# POWER.net
KiCad netlist of a schematic drawn in Altium Designer
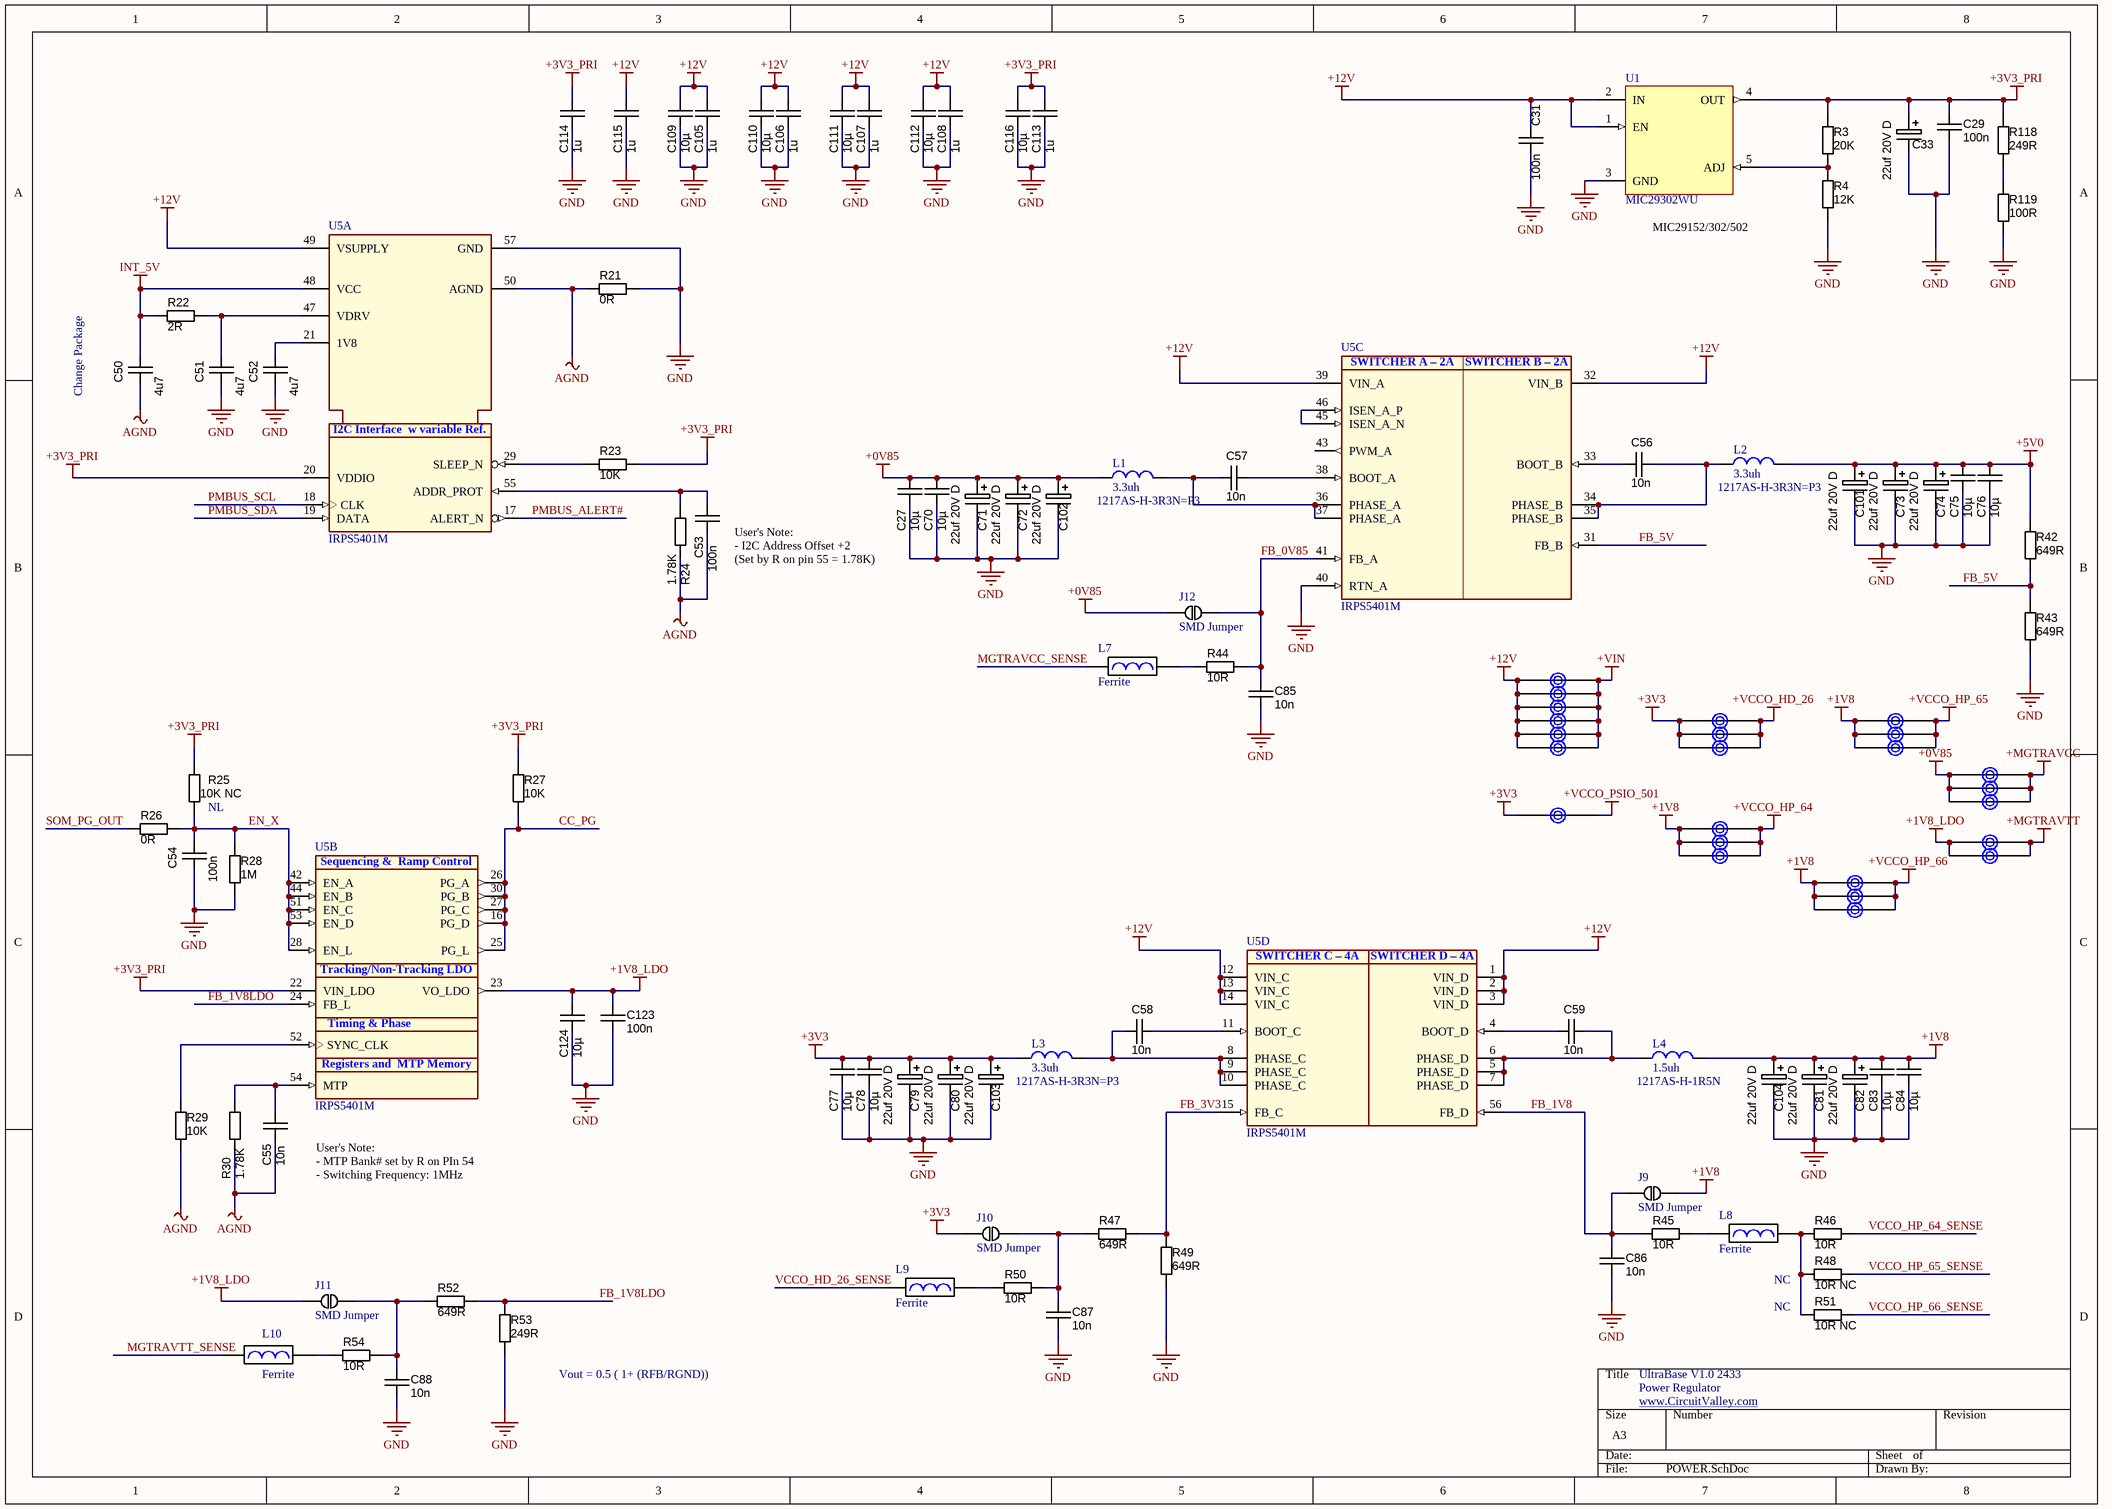
[diagram p0: POWER.SchDoc]

(export (version "E")
  (design (tool "Eeschema 10.0.6"))
  (components
    (comp (ref "C27")
      (value "10µ")
      (footprint "CAPC3225N")
      (description "Capacitor SMD Cer 10uF 20% 16V X5R 1210")
      (fields (field (name "TOLERANCE") "±20%"))
      (libsource (lib "PBL - Capacitors") (part "CAPC_10u_1210_50V"))
    )
    (comp (ref "C29")
      (value "100n")
      (footprint "CAPC1608N")
      (description "Capacitor SMD Cer 1nF 10% 100V X7R 0603")
      (fields (field (name "TOLERANCE") "±10%"))
      (libsource (lib "PBL - Capacitors") (part "CAPC_1n_0603_100V"))
    )
    (comp (ref "C31")
      (value "100n")
      (footprint "CAPC1608N")
      (description "Capacitor SMD Cer 1nF 10% 100V X7R 0603")
      (fields (field (name "TOLERANCE") "±10%"))
      (libsource (lib "PBL - Capacitors") (part "CAPC_1n_0603_100V"))
    )
    (comp (ref "C33")
      (value "22uf 20V D")
      (footprint "CAPMP7343X310N")
      (description "Capacitor SMD Tant 330uF 20% 6V3 2917")
      (fields
        (field (name "TOLERANCE") "±20%")
        (field (name "MANUFACTURER PART NUMBER") "T520D337M006ATE015")
      )
      (libsource (lib "PBL - Capacitors") (part "CAPT_330u_2917_6V3"))
    )
    (comp (ref "C50")
      (value "4u7")
      (footprint "CAPC1608N")
      (description "Capacitor SMD Cer 120pF 10% 50V C0G 0603")
      (fields (field (name "TOLERANCE") "±10%"))
      (libsource (lib "PBL - Capacitors") (part "CAPC_120p_0603_C0G_50V"))
    )
    (comp (ref "C51")
      (value "4u7")
      (footprint "CAPC1608N")
      (description "Capacitor SMD Cer 120pF 10% 50V C0G 0603")
      (fields (field (name "TOLERANCE") "±10%"))
      (libsource (lib "PBL - Capacitors") (part "CAPC_120p_0603_C0G_50V"))
    )
    (comp (ref "C52")
      (value "4u7")
      (footprint "CAPC1608N")
      (description "Capacitor SMD Cer 120pF 10% 50V C0G 0603")
      (fields (field (name "TOLERANCE") "±10%"))
      (libsource (lib "PBL - Capacitors") (part "CAPC_120p_0603_C0G_50V"))
    )
    (comp (ref "C53")
      (value "100n")
      (footprint "CAPC1608N")
      (description "Capacitor SMD Cer 120pF 10% 50V C0G 0603")
      (fields (field (name "TOLERANCE") "±10%"))
      (libsource (lib "PBL - Capacitors") (part "CAPC_120p_0603_C0G_50V"))
    )
    (comp (ref "C54")
      (value "100n")
      (footprint "CAPC1608N")
      (description "Capacitor SMD Cer 120pF 10% 50V C0G 0603")
      (fields (field (name "TOLERANCE") "±10%"))
      (libsource (lib "PBL - Capacitors") (part "CAPC_120p_0603_C0G_50V"))
    )
    (comp (ref "C55")
      (value "10n")
      (footprint "CAPC1608N")
      (description "Capacitor SMD Cer 120pF 10% 50V C0G 0603")
      (fields (field (name "TOLERANCE") "±10%"))
      (libsource (lib "PBL - Capacitors") (part "CAPC_120p_0603_C0G_50V"))
    )
    (comp (ref "C56")
      (value "10n")
      (footprint "CAPC1608N")
      (description "Capacitor SMD Cer 120pF 10% 50V C0G 0603")
      (fields (field (name "TOLERANCE") "±10%"))
      (libsource (lib "PBL - Capacitors") (part "CAPC_120p_0603_C0G_50V"))
    )
    (comp (ref "C57")
      (value "10n")
      (footprint "CAPC1608N")
      (description "Capacitor SMD Cer 120pF 10% 50V C0G 0603")
      (fields (field (name "TOLERANCE") "±10%"))
      (libsource (lib "PBL - Capacitors") (part "CAPC_120p_0603_C0G_50V"))
    )
    (comp (ref "C58")
      (value "10n")
      (footprint "CAPC1608N")
      (description "Capacitor SMD Cer 120pF 10% 50V C0G 0603")
      (fields (field (name "TOLERANCE") "±10%"))
      (libsource (lib "PBL - Capacitors") (part "CAPC_120p_0603_C0G_50V"))
    )
    (comp (ref "C59")
      (value "10n")
      (footprint "CAPC1608N")
      (description "Capacitor SMD Cer 120pF 10% 50V C0G 0603")
      (fields (field (name "TOLERANCE") "±10%"))
      (libsource (lib "PBL - Capacitors") (part "CAPC_120p_0603_C0G_50V"))
    )
    (comp (ref "C70")
      (value "10µ")
      (footprint "CAPC3225N")
      (description "Capacitor SMD Cer 10uF 20% 16V X5R 1210")
      (fields (field (name "TOLERANCE") "±20%"))
      (libsource (lib "PBL - Capacitors") (part "CAPC_10u_1210_50V"))
    )
    (comp (ref "C71")
      (value "22uf 20V D")
      (footprint "CAPMP7343X310N")
      (description "Capacitor SMD Tant 330uF 20% 6V3 2917")
      (fields
        (field (name "TOLERANCE") "±20%")
        (field (name "MANUFACTURER PART NUMBER") "T520D337M006ATE015")
      )
      (libsource (lib "PBL - Capacitors") (part "CAPT_330u_2917_6V3"))
    )
    (comp (ref "C72")
      (value "22uf 20V D")
      (footprint "CAPMP7343X310N")
      (description "Capacitor SMD Tant 330uF 20% 6V3 2917")
      (fields
        (field (name "TOLERANCE") "±20%")
        (field (name "MANUFACTURER PART NUMBER") "T520D337M006ATE015")
      )
      (libsource (lib "PBL - Capacitors") (part "CAPT_330u_2917_6V3"))
    )
    (comp (ref "C73")
      (value "22uf 20V D")
      (footprint "CAPMP7343X310N")
      (description "Capacitor SMD Tant 330uF 20% 6V3 2917")
      (fields
        (field (name "TOLERANCE") "±20%")
        (field (name "MANUFACTURER PART NUMBER") "T520D337M006ATE015")
      )
      (libsource (lib "PBL - Capacitors") (part "CAPT_330u_2917_6V3"))
    )
    (comp (ref "C74")
      (value "22uf 20V D")
      (footprint "CAPMP7343X310N")
      (description "Capacitor SMD Tant 330uF 20% 6V3 2917")
      (fields
        (field (name "TOLERANCE") "±20%")
        (field (name "MANUFACTURER PART NUMBER") "T520D337M006ATE015")
      )
      (libsource (lib "PBL - Capacitors") (part "CAPT_330u_2917_6V3"))
    )
    (comp (ref "C75")
      (value "10µ")
      (footprint "CAPC3225N")
      (description "Capacitor SMD Cer 10uF 20% 16V X5R 1210")
      (fields (field (name "TOLERANCE") "±20%"))
      (libsource (lib "PBL - Capacitors") (part "CAPC_10u_1210_50V"))
    )
    (comp (ref "C76")
      (value "10µ")
      (footprint "CAPC3225N")
      (description "Capacitor SMD Cer 10uF 20% 16V X5R 1210")
      (fields (field (name "TOLERANCE") "±20%"))
      (libsource (lib "PBL - Capacitors") (part "CAPC_10u_1210_50V"))
    )
    (comp (ref "C77")
      (value "10µ")
      (footprint "CAPC3225N")
      (description "Capacitor SMD Cer 10uF 20% 16V X5R 1210")
      (fields (field (name "TOLERANCE") "±20%"))
      (libsource (lib "PBL - Capacitors") (part "CAPC_10u_1210_50V"))
    )
    (comp (ref "C78")
      (value "10µ")
      (footprint "CAPC3225N")
      (description "Capacitor SMD Cer 10uF 20% 16V X5R 1210")
      (fields (field (name "TOLERANCE") "±20%"))
      (libsource (lib "PBL - Capacitors") (part "CAPC_10u_1210_50V"))
    )
    (comp (ref "C79")
      (value "22uf 20V D")
      (footprint "CAPMP7343X310N")
      (description "Capacitor SMD Tant 330uF 20% 6V3 2917")
      (fields
        (field (name "TOLERANCE") "±20%")
        (field (name "MANUFACTURER PART NUMBER") "T520D337M006ATE015")
      )
      (libsource (lib "PBL - Capacitors") (part "CAPT_330u_2917_6V3"))
    )
    (comp (ref "C80")
      (value "22uf 20V D")
      (footprint "CAPMP7343X310N")
      (description "Capacitor SMD Tant 330uF 20% 6V3 2917")
      (fields
        (field (name "TOLERANCE") "±20%")
        (field (name "MANUFACTURER PART NUMBER") "T520D337M006ATE015")
      )
      (libsource (lib "PBL - Capacitors") (part "CAPT_330u_2917_6V3"))
    )
    (comp (ref "C81")
      (value "22uf 20V D")
      (footprint "CAPMP7343X310N")
      (description "Capacitor SMD Tant 330uF 20% 6V3 2917")
      (fields
        (field (name "TOLERANCE") "±20%")
        (field (name "MANUFACTURER PART NUMBER") "T520D337M006ATE015")
      )
      (libsource (lib "PBL - Capacitors") (part "CAPT_330u_2917_6V3"))
    )
    (comp (ref "C82")
      (value "22uf 20V D")
      (footprint "CAPMP7343X310N")
      (description "Capacitor SMD Tant 330uF 20% 6V3 2917")
      (fields
        (field (name "TOLERANCE") "±20%")
        (field (name "MANUFACTURER PART NUMBER") "T520D337M006ATE015")
      )
      (libsource (lib "PBL - Capacitors") (part "CAPT_330u_2917_6V3"))
    )
    (comp (ref "C83")
      (value "10µ")
      (footprint "CAPC3225N")
      (description "Capacitor SMD Cer 10uF 20% 16V X5R 1210")
      (fields (field (name "TOLERANCE") "±20%"))
      (libsource (lib "PBL - Capacitors") (part "CAPC_10u_1210_50V"))
    )
    (comp (ref "C84")
      (value "10µ")
      (footprint "CAPC3225N")
      (description "Capacitor SMD Cer 10uF 20% 16V X5R 1210")
      (fields (field (name "TOLERANCE") "±20%"))
      (libsource (lib "PBL - Capacitors") (part "CAPC_10u_1210_50V"))
    )
    (comp (ref "C85")
      (value "10n")
      (footprint "CAPC1608N")
      (description "Capacitor SMD Cer 120pF 10% 50V C0G 0603")
      (fields (field (name "TOLERANCE") "±10%"))
      (libsource (lib "PBL - Capacitors") (part "CAPC_120p_0603_C0G_50V"))
    )
    (comp (ref "C86")
      (value "10n")
      (footprint "CAPC1608N")
      (description "Capacitor SMD Cer 120pF 10% 50V C0G 0603")
      (fields (field (name "TOLERANCE") "±10%"))
      (libsource (lib "PBL - Capacitors") (part "CAPC_120p_0603_C0G_50V"))
    )
    (comp (ref "C87")
      (value "10n")
      (footprint "CAPC1608N")
      (description "Capacitor SMD Cer 120pF 10% 50V C0G 0603")
      (fields (field (name "TOLERANCE") "±10%"))
      (libsource (lib "PBL - Capacitors") (part "CAPC_120p_0603_C0G_50V"))
    )
    (comp (ref "C88")
      (value "10n")
      (footprint "CAPC1608N")
      (description "Capacitor SMD Cer 120pF 10% 50V C0G 0603")
      (fields (field (name "TOLERANCE") "±10%"))
      (libsource (lib "PBL - Capacitors") (part "CAPC_120p_0603_C0G_50V"))
    )
    (comp (ref "C101")
      (value "22uf 20V D")
      (footprint "CAPMP7343X310N")
      (description "Capacitor SMD Tant 330uF 20% 6V3 2917")
      (fields
        (field (name "TOLERANCE") "±20%")
        (field (name "MANUFACTURER PART NUMBER") "T520D337M006ATE015")
      )
      (libsource (lib "PBL - Capacitors") (part "CAPT_330u_2917_6V3"))
    )
    (comp (ref "C102")
      (value "22uf 20V D")
      (footprint "CAPMP7343X310N")
      (description "Capacitor SMD Tant 330uF 20% 6V3 2917")
      (fields
        (field (name "TOLERANCE") "±20%")
        (field (name "MANUFACTURER PART NUMBER") "T520D337M006ATE015")
      )
      (libsource (lib "PBL - Capacitors") (part "CAPT_330u_2917_6V3"))
    )
    (comp (ref "C103")
      (value "22uf 20V D")
      (footprint "CAPMP7343X310N")
      (description "Capacitor SMD Tant 330uF 20% 6V3 2917")
      (fields
        (field (name "TOLERANCE") "±20%")
        (field (name "MANUFACTURER PART NUMBER") "T520D337M006ATE015")
      )
      (libsource (lib "PBL - Capacitors") (part "CAPT_330u_2917_6V3"))
    )
    (comp (ref "C104")
      (value "22uf 20V D")
      (footprint "CAPMP7343X310N")
      (description "Capacitor SMD Tant 330uF 20% 6V3 2917")
      (fields
        (field (name "TOLERANCE") "±20%")
        (field (name "MANUFACTURER PART NUMBER") "T520D337M006ATE015")
      )
      (libsource (lib "PBL - Capacitors") (part "CAPT_330u_2917_6V3"))
    )
    (comp (ref "C105")
      (value "1u")
      (footprint "CAPC1608N")
      (description "Capacitor SMD Cer 120pF 10% 50V C0G 0603")
      (fields (field (name "TOLERANCE") "±10%"))
      (libsource (lib "PBL - Capacitors") (part "CAPC_120p_0603_C0G_50V"))
    )
    (comp (ref "C106")
      (value "1u")
      (footprint "CAPC1608N")
      (description "Capacitor SMD Cer 120pF 10% 50V C0G 0603")
      (fields (field (name "TOLERANCE") "±10%"))
      (libsource (lib "PBL - Capacitors") (part "CAPC_120p_0603_C0G_50V"))
    )
    (comp (ref "C107")
      (value "1u")
      (footprint "CAPC1608N")
      (description "Capacitor SMD Cer 120pF 10% 50V C0G 0603")
      (fields (field (name "TOLERANCE") "±10%"))
      (libsource (lib "PBL - Capacitors") (part "CAPC_120p_0603_C0G_50V"))
    )
    (comp (ref "C108")
      (value "1u")
      (footprint "CAPC1608N")
      (description "Capacitor SMD Cer 120pF 10% 50V C0G 0603")
      (fields (field (name "TOLERANCE") "±10%"))
      (libsource (lib "PBL - Capacitors") (part "CAPC_120p_0603_C0G_50V"))
    )
    (comp (ref "C109")
      (value "10µ")
      (footprint "CAPC3225N")
      (description "Capacitor SMD Cer 10uF 20% 16V X5R 1210")
      (fields (field (name "TOLERANCE") "±20%"))
      (libsource (lib "PBL - Capacitors") (part "CAPC_10u_1210_50V"))
    )
    (comp (ref "C110")
      (value "10µ")
      (footprint "CAPC3225N")
      (description "Capacitor SMD Cer 10uF 20% 16V X5R 1210")
      (fields (field (name "TOLERANCE") "±20%"))
      (libsource (lib "PBL - Capacitors") (part "CAPC_10u_1210_50V"))
    )
    (comp (ref "C111")
      (value "10µ")
      (footprint "CAPC3225N")
      (description "Capacitor SMD Cer 10uF 20% 16V X5R 1210")
      (fields (field (name "TOLERANCE") "±20%"))
      (libsource (lib "PBL - Capacitors") (part "CAPC_10u_1210_50V"))
    )
    (comp (ref "C112")
      (value "10µ")
      (footprint "CAPC3225N")
      (description "Capacitor SMD Cer 10uF 20% 16V X5R 1210")
      (fields (field (name "TOLERANCE") "±20%"))
      (libsource (lib "PBL - Capacitors") (part "CAPC_10u_1210_50V"))
    )
    (comp (ref "C113")
      (value "1u")
      (footprint "CAPC1608N")
      (description "Capacitor SMD Cer 120pF 10% 50V C0G 0603")
      (fields (field (name "TOLERANCE") "±10%"))
      (libsource (lib "PBL - Capacitors") (part "CAPC_120p_0603_C0G_50V"))
    )
    (comp (ref "C114")
      (value "1u")
      (footprint "CAPC1608N")
      (description "Capacitor SMD Cer 120pF 10% 50V C0G 0603")
      (fields (field (name "TOLERANCE") "±10%"))
      (libsource (lib "PBL - Capacitors") (part "CAPC_120p_0603_C0G_50V"))
    )
    (comp (ref "C115")
      (value "1u")
      (footprint "CAPC1608N")
      (description "Capacitor SMD Cer 120pF 10% 50V C0G 0603")
      (fields (field (name "TOLERANCE") "±10%"))
      (libsource (lib "PBL - Capacitors") (part "CAPC_120p_0603_C0G_50V"))
    )
    (comp (ref "C116")
      (value "10µ")
      (footprint "CAPC3225N")
      (description "Capacitor SMD Cer 10uF 20% 16V X5R 1210")
      (fields (field (name "TOLERANCE") "±20%"))
      (libsource (lib "PBL - Capacitors") (part "CAPC_10u_1210_50V"))
    )
    (comp (ref "C123")
      (value "100n")
      (footprint "CAPC1608N")
      (description "Capacitor SMD Cer 120pF 10% 50V C0G 0603")
      (fields (field (name "TOLERANCE") "±10%"))
      (libsource (lib "PBL - Capacitors") (part "CAPC_120p_0603_C0G_50V"))
    )
    (comp (ref "C124")
      (value "10µ")
      (footprint "CAPC3225N")
      (description "Capacitor SMD Cer 10uF 20% 16V X5R 1210")
      (fields (field (name "TOLERANCE") "±20%"))
      (libsource (lib "PBL - Capacitors") (part "CAPC_10u_1210_50V"))
    )
    (comp (ref "J9")
      (value "SMD Jumper")
      (footprint "SMD_Jumper")
      (libsource (lib "cvlib") (part "SMD_Jumper"))
    )
    (comp (ref "J10")
      (value "SMD Jumper")
      (footprint "SMD_Jumper")
      (libsource (lib "cvlib") (part "SMD_Jumper"))
    )
    (comp (ref "J11")
      (value "SMD Jumper")
      (footprint "SMD_Jumper")
      (libsource (lib "cvlib") (part "SMD_Jumper"))
    )
    (comp (ref "J12")
      (value "SMD Jumper")
      (footprint "SMD_Jumper")
      (libsource (lib "cvlib") (part "SMD_Jumper"))
    )
    (comp (ref "L1")
      (value "3.3uh")
      (footprint "1217AS-H-3R3N=P3")
      (fields (field (name "PART") "1217AS-H-3R3N=P3"))
      (libsource (lib "cvlib") (part "inductor_smd"))
    )
    (comp (ref "L2")
      (value "3.3uh")
      (footprint "1217AS-H-3R3N=P3")
      (fields (field (name "PART") "1217AS-H-3R3N=P3"))
      (libsource (lib "cvlib") (part "inductor_smd"))
    )
    (comp (ref "L3")
      (value "3.3uh")
      (footprint "1217AS-H-3R3N=P3")
      (fields (field (name "PART") "1217AS-H-3R3N=P3"))
      (libsource (lib "cvlib") (part "inductor_smd"))
    )
    (comp (ref "L4")
      (value "1.5uh")
      (footprint "1217AS-H-3R3N=P3")
      (fields (field (name "PART") "1217AS-H-1R5N"))
      (libsource (lib "cvlib") (part "inductor_smd"))
    )
    (comp (ref "L7")
      (value "Ferrite")
      (footprint "FBC2012N")
      (description "Ferrite Bead")
      (libsource (lib "cvlib") (part "Ferrite Bead"))
    )
    (comp (ref "L8")
      (value "Ferrite")
      (footprint "FBC2012N")
      (description "Ferrite Bead")
      (libsource (lib "cvlib") (part "Ferrite Bead"))
    )
    (comp (ref "L9")
      (value "Ferrite")
      (footprint "FBC2012N")
      (description "Ferrite Bead")
      (libsource (lib "cvlib") (part "Ferrite Bead"))
    )
    (comp (ref "L10")
      (value "Ferrite")
      (footprint "FBC2012N")
      (description "Ferrite Bead")
      (libsource (lib "cvlib") (part "Ferrite Bead"))
    )
    (comp (ref "R3")
      (value "20K")
      (footprint "RESC1608N")
      (description "Resistor, SMD chip")
      (fields (field (name "TOLERANCE") "±5%") (field (name "Comment") "RES_NL_0603"))
      (libsource (lib "") (part "RES_NL_0603_1"))
    )
    (comp (ref "R4")
      (value "12K")
      (footprint "RESC1608N")
      (description "Resistor, SMD chip")
      (fields (field (name "TOLERANCE") "±5%") (field (name "Comment") "RES_NL_0603"))
      (libsource (lib "") (part "RES_NL_0603_1"))
    )
    (comp (ref "R21")
      (value "0R")
      (footprint "RESC1608N")
      (description "Resistor, SMD chip")
      (fields (field (name "TOLERANCE") "±5%") (field (name "Comment") "RES_NL_0603"))
      (libsource (lib "PBL - Resistors") (part "RES_NL_0603"))
    )
    (comp (ref "R22")
      (value "2R")
      (footprint "RESC1608N")
      (description "Resistor, SMD chip")
      (fields (field (name "TOLERANCE") "±5%") (field (name "Comment") "RES_NL_0603"))
      (libsource (lib "PBL - Resistors") (part "RES_NL_0603"))
    )
    (comp (ref "R23")
      (value "10K")
      (footprint "RESC1608N")
      (description "Resistor, SMD chip")
      (fields (field (name "TOLERANCE") "±5%") (field (name "Comment") "RES_NL_0603"))
      (libsource (lib "") (part "RES_NL_0603_3"))
    )
    (comp (ref "R24")
      (value "1.78K")
      (footprint "RESC1608N")
      (description "Resistor, SMD chip")
      (fields (field (name "TOLERANCE") "±5%") (field (name "Comment") "RES_NL_0603"))
      (libsource (lib "") (part "RES_NL_0603_2"))
    )
    (comp (ref "R25")
      (value "10K NC")
      (footprint "RESC1608N")
      (description "Resistor, SMD chip")
      (fields (field (name "TOLERANCE") "±5%") (field (name "Comment") "RES_NL_0603"))
      (libsource (lib "") (part "RES_NL_0603_2"))
    )
    (comp (ref "R26")
      (value "0R")
      (footprint "RESC1608N")
      (description "Resistor, SMD chip")
      (fields (field (name "TOLERANCE") "±5%") (field (name "Comment") "RES_NL_0603"))
      (libsource (lib "") (part "RES_NL_0603_3"))
    )
    (comp (ref "R27")
      (value "10K")
      (footprint "RESC1608N")
      (description "Resistor, SMD chip")
      (fields (field (name "TOLERANCE") "±5%") (field (name "Comment") "RES_NL_0603"))
      (libsource (lib "") (part "RES_NL_0603_2"))
    )
    (comp (ref "R28")
      (value "1M")
      (footprint "RESC1608N")
      (description "Resistor, SMD chip")
      (fields (field (name "TOLERANCE") "±5%") (field (name "Comment") "RES_NL_0603"))
      (libsource (lib "") (part "RES_NL_0603_1"))
    )
    (comp (ref "R29")
      (value "10K")
      (footprint "RESC1608N")
      (description "Resistor, SMD chip")
      (fields (field (name "TOLERANCE") "±5%") (field (name "Comment") "RES_NL_0603"))
      (libsource (lib "") (part "RES_NL_0603_1"))
    )
    (comp (ref "R30")
      (value "1.78K")
      (footprint "RESC1608N")
      (description "Resistor, SMD chip")
      (fields (field (name "TOLERANCE") "±5%") (field (name "Comment") "RES_NL_0603"))
      (libsource (lib "") (part "RES_NL_0603_1"))
    )
    (comp (ref "R42")
      (value "649R")
      (footprint "RESC1608N")
      (description "Resistor, SMD chip")
      (fields (field (name "TOLERANCE") "±5%") (field (name "Comment") "RES_NL_0603"))
      (libsource (lib "") (part "RES_NL_0603_1"))
    )
    (comp (ref "R43")
      (value "649R")
      (footprint "RESC1608N")
      (description "Resistor, SMD chip")
      (fields (field (name "TOLERANCE") "±5%") (field (name "Comment") "RES_NL_0603"))
      (libsource (lib "") (part "RES_NL_0603_1"))
    )
    (comp (ref "R44")
      (value "10R")
      (footprint "RESC1608N")
      (description "Resistor, SMD chip")
      (fields (field (name "TOLERANCE") "±5%") (field (name "Comment") "RES_NL_0603"))
      (libsource (lib "PBL - Resistors") (part "RES_NL_0603"))
    )
    (comp (ref "R45")
      (value "10R")
      (footprint "RESC1608N")
      (description "Resistor, SMD chip")
      (fields (field (name "TOLERANCE") "±5%") (field (name "Comment") "RES_NL_0603"))
      (libsource (lib "PBL - Resistors") (part "RES_NL_0603"))
    )
    (comp (ref "R46")
      (value "10R")
      (footprint "RESC1608N")
      (description "Resistor, SMD chip")
      (fields (field (name "TOLERANCE") "±5%") (field (name "Comment") "RES_NL_0603"))
      (libsource (lib "PBL - Resistors") (part "RES_NL_0603"))
    )
    (comp (ref "R47")
      (value "649R")
      (footprint "RESC1608N")
      (description "Resistor, SMD chip")
      (fields (field (name "TOLERANCE") "±5%") (field (name "Comment") "RES_NL_0603"))
      (libsource (lib "PBL - Resistors") (part "RES_NL_0603"))
    )
    (comp (ref "R48")
      (value "10R NC")
      (footprint "RESC1608N")
      (description "Resistor, SMD chip")
      (fields (field (name "TOLERANCE") "±5%") (field (name "Comment") "RES_NL_0603"))
      (libsource (lib "PBL - Resistors") (part "RES_NL_0603"))
    )
    (comp (ref "R49")
      (value "649R")
      (footprint "RESC1608N")
      (description "Resistor, SMD chip")
      (fields (field (name "TOLERANCE") "±5%") (field (name "Comment") "RES_NL_0603"))
      (libsource (lib "") (part "RES_NL_0603_2"))
    )
    (comp (ref "R50")
      (value "10R")
      (footprint "RESC1608N")
      (description "Resistor, SMD chip")
      (fields (field (name "TOLERANCE") "±5%") (field (name "Comment") "RES_NL_0603"))
      (libsource (lib "PBL - Resistors") (part "RES_NL_0603"))
    )
    (comp (ref "R51")
      (value "10R NC")
      (footprint "RESC1608N")
      (description "Resistor, SMD chip")
      (fields (field (name "TOLERANCE") "±5%") (field (name "Comment") "RES_NL_0603"))
      (libsource (lib "PBL - Resistors") (part "RES_NL_0603"))
    )
    (comp (ref "R52")
      (value "649R")
      (footprint "RESC1608N")
      (description "Resistor, SMD chip")
      (fields (field (name "TOLERANCE") "±5%") (field (name "Comment") "RES_NL_0603"))
      (libsource (lib "PBL - Resistors") (part "RES_NL_0603"))
    )
    (comp (ref "R53")
      (value "249R")
      (footprint "RESC1608N")
      (description "Resistor, SMD chip")
      (fields (field (name "TOLERANCE") "±5%") (field (name "Comment") "RES_NL_0603"))
      (libsource (lib "") (part "RES_NL_0603_2"))
    )
    (comp (ref "R54")
      (value "10R")
      (footprint "RESC1608N")
      (description "Resistor, SMD chip")
      (fields (field (name "TOLERANCE") "±5%") (field (name "Comment") "RES_NL_0603"))
      (libsource (lib "PBL - Resistors") (part "RES_NL_0603"))
    )
    (comp (ref "R118")
      (value "249R")
      (footprint "RESC1608N")
      (description "Resistor, SMD chip")
      (fields (field (name "TOLERANCE") "±5%") (field (name "Comment") "RES_NL_0603"))
      (libsource (lib "") (part "RES_NL_0603_1"))
    )
    (comp (ref "R119")
      (value "100R")
      (footprint "RESC1608N")
      (description "Resistor, SMD chip")
      (fields (field (name "TOLERANCE") "±5%") (field (name "Comment") "RES_NL_0603"))
      (libsource (lib "") (part "RES_NL_0603_1"))
    )
    (comp (ref "T1") (value "net_tie") (footprint "net_tie_0mm5") (libsource (lib "cvlib") (part "net_tie")))
    (comp (ref "T2") (value "net_tie") (footprint "net_tie_0mm5") (libsource (lib "cvlib") (part "net_tie")))
    (comp (ref "T3") (value "net_tie") (footprint "net_tie_0mm5") (libsource (lib "cvlib") (part "net_tie")))
    (comp (ref "T4") (value "net_tie") (footprint "net_tie_0mm5") (libsource (lib "cvlib") (part "net_tie")))
    (comp (ref "T5") (value "net_tie") (footprint "net_tie_0mm5") (libsource (lib "cvlib") (part "net_tie")))
    (comp (ref "T6") (value "net_tie") (footprint "net_tie_0mm5") (libsource (lib "cvlib") (part "net_tie")))
    (comp (ref "T7") (value "net_tie") (footprint "net_tie_0mm5") (libsource (lib "cvlib") (part "net_tie")))
    (comp (ref "T8") (value "net_tie") (footprint "net_tie_0mm5") (libsource (lib "cvlib") (part "net_tie")))
    (comp (ref "T9") (value "net_tie") (footprint "net_tie_0mm5") (libsource (lib "cvlib") (part "net_tie")))
    (comp (ref "T10") (value "net_tie") (footprint "net_tie_0mm5") (libsource (lib "cvlib") (part "net_tie")))
    (comp (ref "T11") (value "net_tie") (footprint "net_tie_0mm5") (libsource (lib "cvlib") (part "net_tie")))
    (comp (ref "T12") (value "net_tie") (footprint "net_tie_0mm5") (libsource (lib "cvlib") (part "net_tie")))
    (comp (ref "T13") (value "net_tie") (footprint "net_tie_0mm5") (libsource (lib "cvlib") (part "net_tie")))
    (comp (ref "T14") (value "net_tie") (footprint "net_tie_0mm5") (libsource (lib "cvlib") (part "net_tie")))
    (comp (ref "T15") (value "net_tie") (footprint "net_tie_0mm5") (libsource (lib "cvlib") (part "net_tie")))
    (comp (ref "T16") (value "net_tie") (footprint "net_tie_0mm5") (libsource (lib "cvlib") (part "net_tie")))
    (comp (ref "T17") (value "net_tie") (footprint "net_tie_0mm5") (libsource (lib "cvlib") (part "net_tie")))
    (comp (ref "T18") (value "net_tie") (footprint "net_tie_0mm5") (libsource (lib "cvlib") (part "net_tie")))
    (comp (ref "T19") (value "net_tie") (footprint "net_tie_0mm5") (libsource (lib "cvlib") (part "net_tie")))
    (comp (ref "T20") (value "net_tie") (footprint "net_tie_0mm5") (libsource (lib "cvlib") (part "net_tie")))
    (comp (ref "T21") (value "net_tie") (footprint "net_tie_0mm5") (libsource (lib "cvlib") (part "net_tie")))
    (comp (ref "T22") (value "net_tie") (footprint "net_tie_0mm5") (libsource (lib "cvlib") (part "net_tie")))
    (comp (ref "T23") (value "net_tie") (footprint "net_tie_0mm5") (libsource (lib "cvlib") (part "net_tie")))
    (comp (ref "T24") (value "net_tie") (footprint "net_tie_0mm5") (libsource (lib "cvlib") (part "net_tie")))
    (comp (ref "U1")
      (value "MIC29302WU")
      (footprint "TO-263-5")
      (libsource (lib "cvlib") (part "MIC29302WU"))
    )
    (comp (ref "U5")
      (value "IRPS5401M")
      (footprint "INF-PG-QFN-56-7X7")
      (description "PMIC Flexible Power Management Unit")
      (fields (field (name "MANUFACTURER") "Infineon Technologies"))
      (libsource (lib "cvlib") (part "IRPS5401M"))
    )
  )
  (nets
    (net (code "1") (name "+0V85") (class "Default")
      (node (ref "C102") (pin "1") (pintype "passive"))
      (node (ref "C27") (pin "1") (pintype "passive"))
      (node (ref "C70") (pin "1") (pintype "passive"))
      (node (ref "C71") (pin "1") (pintype "passive"))
      (node (ref "C72") (pin "1") (pintype "passive"))
      (node (ref "J12") (pin "1") (pinfunction "1_1") (pintype "passive"))
      (node (ref "L1") (pin "1") (pinfunction "1_1") (pintype "passive"))
      (node (ref "T10") (pin "1") (pinfunction "PAD_1") (pintype "passive"))
      (node (ref "T8") (pin "1") (pinfunction "PAD_1") (pintype "passive"))
      (node (ref "T9") (pin "1") (pinfunction "PAD_1") (pintype "passive"))
    )
    (net (code "2") (name "+1V8") (class "Default")
      (node (ref "C104") (pin "1") (pintype "passive"))
      (node (ref "C81") (pin "1") (pintype "passive"))
      (node (ref "C82") (pin "1") (pintype "passive"))
      (node (ref "C83") (pin "1") (pintype "passive"))
      (node (ref "C84") (pin "1") (pintype "passive"))
      (node (ref "J9") (pin "2") (pinfunction "2_2") (pintype "passive"))
      (node (ref "L4") (pin "2") (pinfunction "2_2") (pintype "passive"))
      (node (ref "T12") (pin "1") (pinfunction "PAD_1") (pintype "passive"))
      (node (ref "T13") (pin "1") (pinfunction "PAD_1") (pintype "passive"))
      (node (ref "T15") (pin "1") (pinfunction "PAD_1") (pintype "passive"))
      (node (ref "T17") (pin "1") (pinfunction "PAD_1") (pintype "passive"))
      (node (ref "T18") (pin "1") (pinfunction "PAD_1") (pintype "passive"))
      (node (ref "T19") (pin "1") (pinfunction "PAD_1") (pintype "passive"))
      (node (ref "T3") (pin "1") (pinfunction "PAD_1") (pintype "passive"))
      (node (ref "T5") (pin "1") (pinfunction "PAD_1") (pintype "passive"))
      (node (ref "T7") (pin "1") (pinfunction "PAD_1") (pintype "passive"))
    )
    (net (code "3") (name "+1V8_LDO") (class "Default")
      (node (ref "C123") (pin "2") (pintype "passive"))
      (node (ref "C124") (pin "1") (pintype "passive"))
      (node (ref "J11") (pin "1") (pinfunction "1_1") (pintype "passive"))
      (node (ref "T14") (pin "1") (pinfunction "PAD_1") (pintype "passive"))
      (node (ref "T16") (pin "1") (pinfunction "PAD_1") (pintype "passive"))
      (node (ref "U5") (pin "23") (pinfunction "VO_LDO_23") (pintype "output"))
    )
    (net (code "4") (name "+3V3") (class "Default")
      (node (ref "C103") (pin "1") (pintype "passive"))
      (node (ref "C77") (pin "1") (pintype "passive"))
      (node (ref "C78") (pin "1") (pintype "passive"))
      (node (ref "C79") (pin "1") (pintype "passive"))
      (node (ref "C80") (pin "1") (pintype "passive"))
      (node (ref "J10") (pin "1") (pinfunction "1_1") (pintype "passive"))
      (node (ref "L3") (pin "1") (pinfunction "1_1") (pintype "passive"))
      (node (ref "T11") (pin "1") (pinfunction "PAD_1") (pintype "passive"))
      (node (ref "T2") (pin "1") (pinfunction "PAD_1") (pintype "passive"))
      (node (ref "T4") (pin "1") (pinfunction "PAD_1") (pintype "passive"))
      (node (ref "T6") (pin "1") (pinfunction "PAD_1") (pintype "passive"))
    )
    (net (code "5") (name "+3V3_PRI") (class "Default")
      (node (ref "C113") (pin "2") (pintype "passive"))
      (node (ref "C114") (pin "2") (pintype "passive"))
      (node (ref "C116") (pin "1") (pintype "passive"))
      (node (ref "C29") (pin "1") (pintype "passive"))
      (node (ref "C33") (pin "1") (pintype "passive"))
      (node (ref "R118") (pin "1") (pinfunction "1_1") (pintype "passive"))
      (node (ref "R23") (pin "1") (pinfunction "1_1") (pintype "passive"))
      (node (ref "R25") (pin "2") (pinfunction "2_2") (pintype "passive"))
      (node (ref "R27") (pin "2") (pinfunction "2_2") (pintype "passive"))
      (node (ref "R3") (pin "1") (pinfunction "1_1") (pintype "passive"))
      (node (ref "U1") (pin "4") (pinfunction "OUT_4") (pintype "output"))
      (node (ref "U5") (pin "20") (pinfunction "VDDIO_20") (pintype "power_in"))
      (node (ref "U5") (pin "22") (pinfunction "VIN_LDO_22") (pintype "power_in"))
    )
    (net (code "6") (name "+5V0") (class "Default")
      (node (ref "C101") (pin "1") (pintype "passive"))
      (node (ref "C73") (pin "1") (pintype "passive"))
      (node (ref "C74") (pin "1") (pintype "passive"))
      (node (ref "C75") (pin "1") (pintype "passive"))
      (node (ref "C76") (pin "1") (pintype "passive"))
      (node (ref "L2") (pin "2") (pinfunction "2_2") (pintype "passive"))
      (node (ref "R42") (pin "1") (pinfunction "1_1") (pintype "passive"))
    )
    (net (code "7") (name "+12V") (class "Default")
      (node (ref "C105") (pin "2") (pintype "passive"))
      (node (ref "C106") (pin "2") (pintype "passive"))
      (node (ref "C107") (pin "2") (pintype "passive"))
      (node (ref "C108") (pin "2") (pintype "passive"))
      (node (ref "C109") (pin "1") (pintype "passive"))
      (node (ref "C110") (pin "1") (pintype "passive"))
      (node (ref "C111") (pin "1") (pintype "passive"))
      (node (ref "C112") (pin "1") (pintype "passive"))
      (node (ref "C115") (pin "2") (pintype "passive"))
      (node (ref "C31") (pin "1") (pintype "passive"))
      (node (ref "T1") (pin "1") (pinfunction "PAD_1") (pintype "passive"))
      (node (ref "T20") (pin "1") (pinfunction "PAD_1") (pintype "passive"))
      (node (ref "T21") (pin "1") (pinfunction "PAD_1") (pintype "passive"))
      (node (ref "T22") (pin "1") (pinfunction "PAD_1") (pintype "passive"))
      (node (ref "T23") (pin "1") (pinfunction "PAD_1") (pintype "passive"))
      (node (ref "T24") (pin "1") (pinfunction "PAD_1") (pintype "passive"))
      (node (ref "U1") (pin "1") (pinfunction "EN_1") (pintype "input"))
      (node (ref "U1") (pin "2") (pinfunction "IN_2") (pintype "power_in"))
      (node (ref "U5") (pin "1") (pinfunction "VIN_D_1") (pintype "power_in"))
      (node (ref "U5") (pin "12") (pinfunction "VIN_C_12") (pintype "power_in"))
      (node (ref "U5") (pin "13") (pinfunction "VIN_C_13") (pintype "power_in"))
      (node (ref "U5") (pin "14") (pinfunction "VIN_C_14") (pintype "power_in"))
      (node (ref "U5") (pin "2") (pinfunction "VIN_D_2") (pintype "power_in"))
      (node (ref "U5") (pin "3") (pinfunction "VIN_D_3") (pintype "power_in"))
      (node (ref "U5") (pin "32") (pinfunction "VIN_B_32") (pintype "power_in"))
      (node (ref "U5") (pin "39") (pinfunction "VIN_A_39") (pintype "power_in"))
      (node (ref "U5") (pin "49") (pinfunction "VSUPPLY_49") (pintype "power_in"))
    )
    (net (code "8") (name "+MGTRAVCC") (class "Default")
      (node (ref "T10") (pin "2") (pinfunction "PAD_2") (pintype "passive"))
      (node (ref "T8") (pin "2") (pinfunction "PAD_2") (pintype "passive"))
      (node (ref "T9") (pin "2") (pinfunction "PAD_2") (pintype "passive"))
    )
    (net (code "9") (name "+MGTRAVTT") (class "Default")
      (node (ref "T14") (pin "2") (pinfunction "PAD_2") (pintype "passive"))
      (node (ref "T16") (pin "2") (pinfunction "PAD_2") (pintype "passive"))
    )
    (net (code "10") (name "+VCCO_HD_26") (class "Default")
      (node (ref "T2") (pin "2") (pinfunction "PAD_2") (pintype "passive"))
      (node (ref "T4") (pin "2") (pinfunction "PAD_2") (pintype "passive"))
      (node (ref "T6") (pin "2") (pinfunction "PAD_2") (pintype "passive"))
    )
    (net (code "11") (name "+VCCO_HP_64") (class "Default")
      (node (ref "T12") (pin "2") (pinfunction "PAD_2") (pintype "passive"))
      (node (ref "T13") (pin "2") (pinfunction "PAD_2") (pintype "passive"))
      (node (ref "T15") (pin "2") (pinfunction "PAD_2") (pintype "passive"))
    )
    (net (code "12") (name "+VCCO_HP_65") (class "Default")
      (node (ref "T3") (pin "2") (pinfunction "PAD_2") (pintype "passive"))
      (node (ref "T5") (pin "2") (pinfunction "PAD_2") (pintype "passive"))
      (node (ref "T7") (pin "2") (pinfunction "PAD_2") (pintype "passive"))
    )
    (net (code "13") (name "+VCCO_HP_66") (class "Default")
      (node (ref "T17") (pin "2") (pinfunction "PAD_2") (pintype "passive"))
      (node (ref "T18") (pin "2") (pinfunction "PAD_2") (pintype "passive"))
      (node (ref "T19") (pin "2") (pinfunction "PAD_2") (pintype "passive"))
    )
    (net (code "14") (name "+VCCO_PSIO_501") (class "Default")
      (node (ref "T11") (pin "2") (pinfunction "PAD_2") (pintype "passive"))
    )
    (net (code "15") (name "+VIN") (class "Default")
      (node (ref "T1") (pin "2") (pinfunction "PAD_2") (pintype "passive"))
      (node (ref "T20") (pin "2") (pinfunction "PAD_2") (pintype "passive"))
      (node (ref "T21") (pin "2") (pinfunction "PAD_2") (pintype "passive"))
      (node (ref "T22") (pin "2") (pinfunction "PAD_2") (pintype "passive"))
      (node (ref "T23") (pin "2") (pinfunction "PAD_2") (pintype "passive"))
      (node (ref "T24") (pin "2") (pinfunction "PAD_2") (pintype "passive"))
    )
    (net (code "16") (name "/CC_PG") (class "Default")
      (node (ref "R27") (pin "1") (pinfunction "1_1") (pintype "passive"))
      (node (ref "U5") (pin "16") (pinfunction "PG_D_16") (pintype "output"))
      (node (ref "U5") (pin "25") (pinfunction "PG_L_25") (pintype "output"))
      (node (ref "U5") (pin "26") (pinfunction "PG_A_26") (pintype "output"))
      (node (ref "U5") (pin "27") (pinfunction "PG_C_27") (pintype "output"))
      (node (ref "U5") (pin "30") (pinfunction "PG_B_30") (pintype "output"))
    )
    (net (code "17") (name "/EN_X") (class "Default")
      (node (ref "C54") (pin "1") (pintype "passive"))
      (node (ref "R25") (pin "1") (pinfunction "1_1") (pintype "passive"))
      (node (ref "R26") (pin "1") (pinfunction "1_1") (pintype "passive"))
      (node (ref "R28") (pin "1") (pinfunction "1_1") (pintype "passive"))
      (node (ref "U5") (pin "28") (pinfunction "EN_L_28") (pintype "input"))
      (node (ref "U5") (pin "42") (pinfunction "EN_A_42") (pintype "input"))
      (node (ref "U5") (pin "44") (pinfunction "EN_B_44") (pintype "input"))
      (node (ref "U5") (pin "51") (pinfunction "EN_C_51") (pintype "input"))
      (node (ref "U5") (pin "53") (pinfunction "EN_D_53") (pintype "input"))
    )
    (net (code "18") (name "/FB_0V85") (class "Default")
      (node (ref "C85") (pin "2") (pintype "passive"))
      (node (ref "J12") (pin "2") (pinfunction "2_2") (pintype "passive"))
      (node (ref "R44") (pin "2") (pinfunction "2_2") (pintype "passive"))
      (node (ref "U5") (pin "41") (pinfunction "FB_A_41") (pintype "input"))
    )
    (net (code "19") (name "/FB_1V8") (class "Default")
      (node (ref "C86") (pin "2") (pintype "passive"))
      (node (ref "J9") (pin "1") (pinfunction "1_1") (pintype "passive"))
      (node (ref "R45") (pin "1") (pinfunction "1_1") (pintype "passive"))
      (node (ref "U5") (pin "56") (pinfunction "FB_D_56") (pintype "input"))
    )
    (net (code "20") (name "/FB_1V8LDO") (class "Default")
      (node (ref "R52") (pin "2") (pinfunction "2_2") (pintype "passive"))
      (node (ref "R53") (pin "2") (pinfunction "2_2") (pintype "passive"))
      (node (ref "U5") (pin "24") (pinfunction "FB_L_24") (pintype "input"))
    )
    (net (code "21") (name "/FB_3V3") (class "Default")
      (node (ref "R47") (pin "2") (pinfunction "2_2") (pintype "passive"))
      (node (ref "R49") (pin "2") (pinfunction "2_2") (pintype "passive"))
      (node (ref "U5") (pin "15") (pinfunction "FB_C_15") (pintype "input"))
    )
    (net (code "22") (name "/FB_5V") (class "Default")
      (node (ref "R42") (pin "2") (pinfunction "2_2") (pintype "passive"))
      (node (ref "R43") (pin "1") (pinfunction "1_1") (pintype "passive"))
      (node (ref "U5") (pin "31") (pinfunction "FB_B_31") (pintype "input"))
    )
    (net (code "23") (name "/MGTRAVCC_SENSE") (class "Default")
      (node (ref "L7") (pin "1") (pinfunction "1_1") (pintype "passive"))
    )
    (net (code "24") (name "/MGTRAVTT_SENSE") (class "Default")
      (node (ref "L10") (pin "1") (pinfunction "1_1") (pintype "passive"))
    )
    (net (code "25") (name "/PMBUS_ALERT#") (class "Default")
      (node (ref "U5") (pin "17") (pinfunction "ALERT_N_17") (pintype "output"))
    )
    (net (code "26") (name "/PMBUS_SCL") (class "Default")
      (node (ref "U5") (pin "18") (pinfunction "CLK_18") (pintype "input"))
    )
    (net (code "27") (name "/PMBUS_SDA") (class "Default")
      (node (ref "U5") (pin "19") (pinfunction "DATA_19") (pintype "input"))
    )
    (net (code "28") (name "/SOM_PG_OUT") (class "Default")
      (node (ref "R26") (pin "2") (pinfunction "2_2") (pintype "passive"))
    )
    (net (code "29") (name "/VCCO_HD_26_SENSE") (class "Default")
      (node (ref "L9") (pin "1") (pinfunction "1_1") (pintype "passive"))
    )
    (net (code "30") (name "/VCCO_HP_64_SENSE") (class "Default")
      (node (ref "R46") (pin "2") (pinfunction "2_2") (pintype "passive"))
    )
    (net (code "31") (name "/VCCO_HP_65_SENSE") (class "Default")
      (node (ref "R48") (pin "2") (pinfunction "2_2") (pintype "passive"))
    )
    (net (code "32") (name "/VCCO_HP_66_SENSE") (class "Default")
      (node (ref "R51") (pin "2") (pinfunction "2_2") (pintype "passive"))
    )
    (net (code "33") (name "AGND") (class "Default")
      (node (ref "C50") (pin "2") (pintype "passive"))
      (node (ref "C53") (pin "2") (pintype "passive"))
      (node (ref "C55") (pin "2") (pintype "passive"))
      (node (ref "R21") (pin "1") (pinfunction "1_1") (pintype "passive"))
      (node (ref "R24") (pin "1") (pinfunction "1_1") (pintype "passive"))
      (node (ref "R29") (pin "2") (pinfunction "2_2") (pintype "passive"))
      (node (ref "R30") (pin "2") (pinfunction "2_2") (pintype "passive"))
      (node (ref "U5") (pin "50") (pinfunction "AGND_50") (pintype "power_in"))
    )
    (net (code "34") (name "GND") (class "Default")
      (node (ref "C101") (pin "2") (pintype "passive"))
      (node (ref "C102") (pin "2") (pintype "passive"))
      (node (ref "C103") (pin "2") (pintype "passive"))
      (node (ref "C104") (pin "2") (pintype "passive"))
      (node (ref "C105") (pin "1") (pintype "passive"))
      (node (ref "C106") (pin "1") (pintype "passive"))
      (node (ref "C107") (pin "1") (pintype "passive"))
      (node (ref "C108") (pin "1") (pintype "passive"))
      (node (ref "C109") (pin "2") (pintype "passive"))
      (node (ref "C110") (pin "2") (pintype "passive"))
      (node (ref "C111") (pin "2") (pintype "passive"))
      (node (ref "C112") (pin "2") (pintype "passive"))
      (node (ref "C113") (pin "1") (pintype "passive"))
      (node (ref "C114") (pin "1") (pintype "passive"))
      (node (ref "C115") (pin "1") (pintype "passive"))
      (node (ref "C116") (pin "2") (pintype "passive"))
      (node (ref "C123") (pin "1") (pintype "passive"))
      (node (ref "C124") (pin "2") (pintype "passive"))
      (node (ref "C27") (pin "2") (pintype "passive"))
      (node (ref "C29") (pin "2") (pintype "passive"))
      (node (ref "C31") (pin "2") (pintype "passive"))
      (node (ref "C33") (pin "2") (pintype "passive"))
      (node (ref "C51") (pin "2") (pintype "passive"))
      (node (ref "C52") (pin "2") (pintype "passive"))
      (node (ref "C54") (pin "2") (pintype "passive"))
      (node (ref "C70") (pin "2") (pintype "passive"))
      (node (ref "C71") (pin "2") (pintype "passive"))
      (node (ref "C72") (pin "2") (pintype "passive"))
      (node (ref "C73") (pin "2") (pintype "passive"))
      (node (ref "C74") (pin "2") (pintype "passive"))
      (node (ref "C75") (pin "2") (pintype "passive"))
      (node (ref "C76") (pin "2") (pintype "passive"))
      (node (ref "C77") (pin "2") (pintype "passive"))
      (node (ref "C78") (pin "2") (pintype "passive"))
      (node (ref "C79") (pin "2") (pintype "passive"))
      (node (ref "C80") (pin "2") (pintype "passive"))
      (node (ref "C81") (pin "2") (pintype "passive"))
      (node (ref "C82") (pin "2") (pintype "passive"))
      (node (ref "C83") (pin "2") (pintype "passive"))
      (node (ref "C84") (pin "2") (pintype "passive"))
      (node (ref "C85") (pin "1") (pintype "passive"))
      (node (ref "C86") (pin "1") (pintype "passive"))
      (node (ref "C87") (pin "1") (pintype "passive"))
      (node (ref "C88") (pin "1") (pintype "passive"))
      (node (ref "R119") (pin "2") (pinfunction "2_2") (pintype "passive"))
      (node (ref "R21") (pin "2") (pinfunction "2_2") (pintype "passive"))
      (node (ref "R28") (pin "2") (pinfunction "2_2") (pintype "passive"))
      (node (ref "R4") (pin "2") (pinfunction "2_2") (pintype "passive"))
      (node (ref "R43") (pin "2") (pinfunction "2_2") (pintype "passive"))
      (node (ref "R49") (pin "1") (pinfunction "1_1") (pintype "passive"))
      (node (ref "R53") (pin "1") (pinfunction "1_1") (pintype "passive"))
      (node (ref "U1") (pin "3") (pinfunction "GND_3") (pintype "power_in"))
      (node (ref "U5") (pin "40") (pinfunction "RTN_A_40") (pintype "input"))
      (node (ref "U5") (pin "57") (pinfunction "GND_57") (pintype "power_in"))
    )
    (net (code "35") (name "INT_5V") (class "Default")
      (node (ref "C50") (pin "1") (pintype "passive"))
      (node (ref "R22") (pin "1") (pinfunction "1_1") (pintype "passive"))
      (node (ref "U5") (pin "48") (pinfunction "VCC_48") (pintype "power_in"))
    )
    (net (code "36") (name "Net-(C56-Pad2)") (class "Default")
      (node (ref "C56") (pin "2") (pintype "passive"))
      (node (ref "L2") (pin "1") (pinfunction "1_1") (pintype "passive"))
      (node (ref "U5") (pin "34") (pinfunction "PHASE_B_34") (pintype "power_in"))
      (node (ref "U5") (pin "35") (pinfunction "PHASE_B_35") (pintype "power_in"))
    )
    (net (code "37") (name "Net-(C57-Pad1)") (class "Default")
      (node (ref "C57") (pin "1") (pintype "passive"))
      (node (ref "L1") (pin "2") (pinfunction "2_2") (pintype "passive"))
      (node (ref "U5") (pin "36") (pinfunction "PHASE_A_36") (pintype "power_in"))
      (node (ref "U5") (pin "37") (pinfunction "PHASE_A_37") (pintype "power_in"))
    )
    (net (code "38") (name "Net-(C58-Pad1)") (class "Default")
      (node (ref "C58") (pin "1") (pintype "passive"))
      (node (ref "L3") (pin "2") (pinfunction "2_2") (pintype "passive"))
      (node (ref "U5") (pin "10") (pinfunction "PHASE_C_10") (pintype "power_in"))
      (node (ref "U5") (pin "8") (pinfunction "PHASE_C_8") (pintype "power_in"))
      (node (ref "U5") (pin "9") (pinfunction "PHASE_C_9") (pintype "power_in"))
    )
    (net (code "39") (name "Net-(C59-Pad2)") (class "Default")
      (node (ref "C59") (pin "2") (pintype "passive"))
      (node (ref "L4") (pin "1") (pinfunction "1_1") (pintype "passive"))
      (node (ref "U5") (pin "5") (pinfunction "PHASE_D_5") (pintype "power_in"))
      (node (ref "U5") (pin "6") (pinfunction "PHASE_D_6") (pintype "power_in"))
      (node (ref "U5") (pin "7") (pinfunction "PHASE_D_7") (pintype "power_in"))
    )
    (net (code "40") (name "Net-(C87-Pad2)") (class "Default")
      (node (ref "C87") (pin "2") (pintype "passive"))
      (node (ref "J10") (pin "2") (pinfunction "2_2") (pintype "passive"))
      (node (ref "R47") (pin "1") (pinfunction "1_1") (pintype "passive"))
      (node (ref "R50") (pin "2") (pinfunction "2_2") (pintype "passive"))
    )
    (net (code "41") (name "Net-(C88-Pad2)") (class "Default")
      (node (ref "C88") (pin "2") (pintype "passive"))
      (node (ref "J11") (pin "2") (pinfunction "2_2") (pintype "passive"))
      (node (ref "R52") (pin "1") (pinfunction "1_1") (pintype "passive"))
      (node (ref "R54") (pin "2") (pinfunction "2_2") (pintype "passive"))
    )
    (net (code "42") (name "Net-(L7-Pad2)") (class "Default")
      (node (ref "L7") (pin "2") (pinfunction "2_2") (pintype "passive"))
      (node (ref "R44") (pin "1") (pinfunction "1_1") (pintype "passive"))
    )
    (net (code "43") (name "Net-(L8-Pad1)") (class "Default")
      (node (ref "L8") (pin "1") (pinfunction "1_1") (pintype "passive"))
      (node (ref "R45") (pin "2") (pinfunction "2_2") (pintype "passive"))
    )
    (net (code "44") (name "Net-(L8-Pad2)") (class "Default")
      (node (ref "L8") (pin "2") (pinfunction "2_2") (pintype "passive"))
      (node (ref "R46") (pin "1") (pinfunction "1_1") (pintype "passive"))
      (node (ref "R48") (pin "1") (pinfunction "1_1") (pintype "passive"))
      (node (ref "R51") (pin "1") (pinfunction "1_1") (pintype "passive"))
    )
    (net (code "45") (name "Net-(L9-Pad2)") (class "Default")
      (node (ref "L9") (pin "2") (pinfunction "2_2") (pintype "passive"))
      (node (ref "R50") (pin "1") (pinfunction "1_1") (pintype "passive"))
    )
    (net (code "46") (name "Net-(L10-Pad2)") (class "Default")
      (node (ref "L10") (pin "2") (pinfunction "2_2") (pintype "passive"))
      (node (ref "R54") (pin "1") (pinfunction "1_1") (pintype "passive"))
    )
    (net (code "47") (name "Net-(R118-Pad2)") (class "Default")
      (node (ref "R118") (pin "2") (pinfunction "2_2") (pintype "passive"))
      (node (ref "R119") (pin "1") (pinfunction "1_1") (pintype "passive"))
    )
    (net (code "48") (name "Net-(U1-ADJ)") (class "Default")
      (node (ref "R3") (pin "2") (pinfunction "2_2") (pintype "passive"))
      (node (ref "R4") (pin "1") (pinfunction "1_1") (pintype "passive"))
      (node (ref "U1") (pin "5") (pinfunction "ADJ_5") (pintype "input"))
    )
    (net (code "49") (name "Net-(U5A-1V8)") (class "Default")
      (node (ref "C52") (pin "1") (pintype "passive"))
      (node (ref "U5") (pin "21") (pinfunction "1V8_21") (pintype "power_in"))
    )
    (net (code "50") (name "Net-(U5A-ADDR_PROT)") (class "Default")
      (node (ref "C53") (pin "1") (pintype "passive"))
      (node (ref "R24") (pin "2") (pinfunction "2_2") (pintype "passive"))
      (node (ref "U5") (pin "55") (pinfunction "ADDR_PROT_55") (pintype "input"))
    )
    (net (code "51") (name "Net-(U5A-SLEEP_N)") (class "Default")
      (node (ref "R23") (pin "2") (pinfunction "2_2") (pintype "passive"))
      (node (ref "U5") (pin "29") (pinfunction "SLEEP_N_29") (pintype "input"))
    )
    (net (code "52") (name "Net-(U5A-VDRV)") (class "Default")
      (node (ref "C51") (pin "1") (pintype "passive"))
      (node (ref "R22") (pin "2") (pinfunction "2_2") (pintype "passive"))
      (node (ref "U5") (pin "47") (pinfunction "VDRV_47") (pintype "power_in"))
    )
    (net (code "53") (name "Net-(U5B-MTP)") (class "Default")
      (node (ref "C55") (pin "1") (pintype "passive"))
      (node (ref "R30") (pin "1") (pinfunction "1_1") (pintype "passive"))
      (node (ref "U5") (pin "54") (pinfunction "MTP_54") (pintype "input"))
    )
    (net (code "54") (name "Net-(U5B-SYNC_CLK)") (class "Default")
      (node (ref "R29") (pin "1") (pinfunction "1_1") (pintype "passive"))
      (node (ref "U5") (pin "52") (pinfunction "SYNC_CLK_52") (pintype "input"))
    )
    (net (code "55") (name "Net-(U5C-BOOT_A)") (class "Default")
      (node (ref "C57") (pin "2") (pintype "passive"))
      (node (ref "U5") (pin "38") (pinfunction "BOOT_A_38") (pintype "input"))
    )
    (net (code "56") (name "Net-(U5C-BOOT_B)") (class "Default")
      (node (ref "C56") (pin "1") (pintype "passive"))
      (node (ref "U5") (pin "33") (pinfunction "BOOT_B_33") (pintype "input"))
    )
    (net (code "57") (name "Net-(U5C-ISEN_A_N)") (class "Default")
      (node (ref "U5") (pin "45") (pinfunction "ISEN_A_N_45") (pintype "input"))
      (node (ref "U5") (pin "46") (pinfunction "ISEN_A_P_46") (pintype "input"))
    )
    (net (code "58") (name "Net-(U5D-BOOT_C)") (class "Default")
      (node (ref "C58") (pin "2") (pintype "passive"))
      (node (ref "U5") (pin "11") (pinfunction "BOOT_C_11") (pintype "input"))
    )
    (net (code "59") (name "Net-(U5D-BOOT_D)") (class "Default")
      (node (ref "C59") (pin "1") (pintype "passive"))
      (node (ref "U5") (pin "4") (pinfunction "BOOT_D_4") (pintype "input"))
    )
    (net (code "60") (name "unconnected-(U5C-PWM_A-Pad43)") (class "Default")
      (node (ref "U5") (pin "43") (pinfunction "PWM_A_43") (pintype "output"))
    )
  )
)
